# Sensor8A.net
KiCad netlist of a schematic drawn in EAGLE
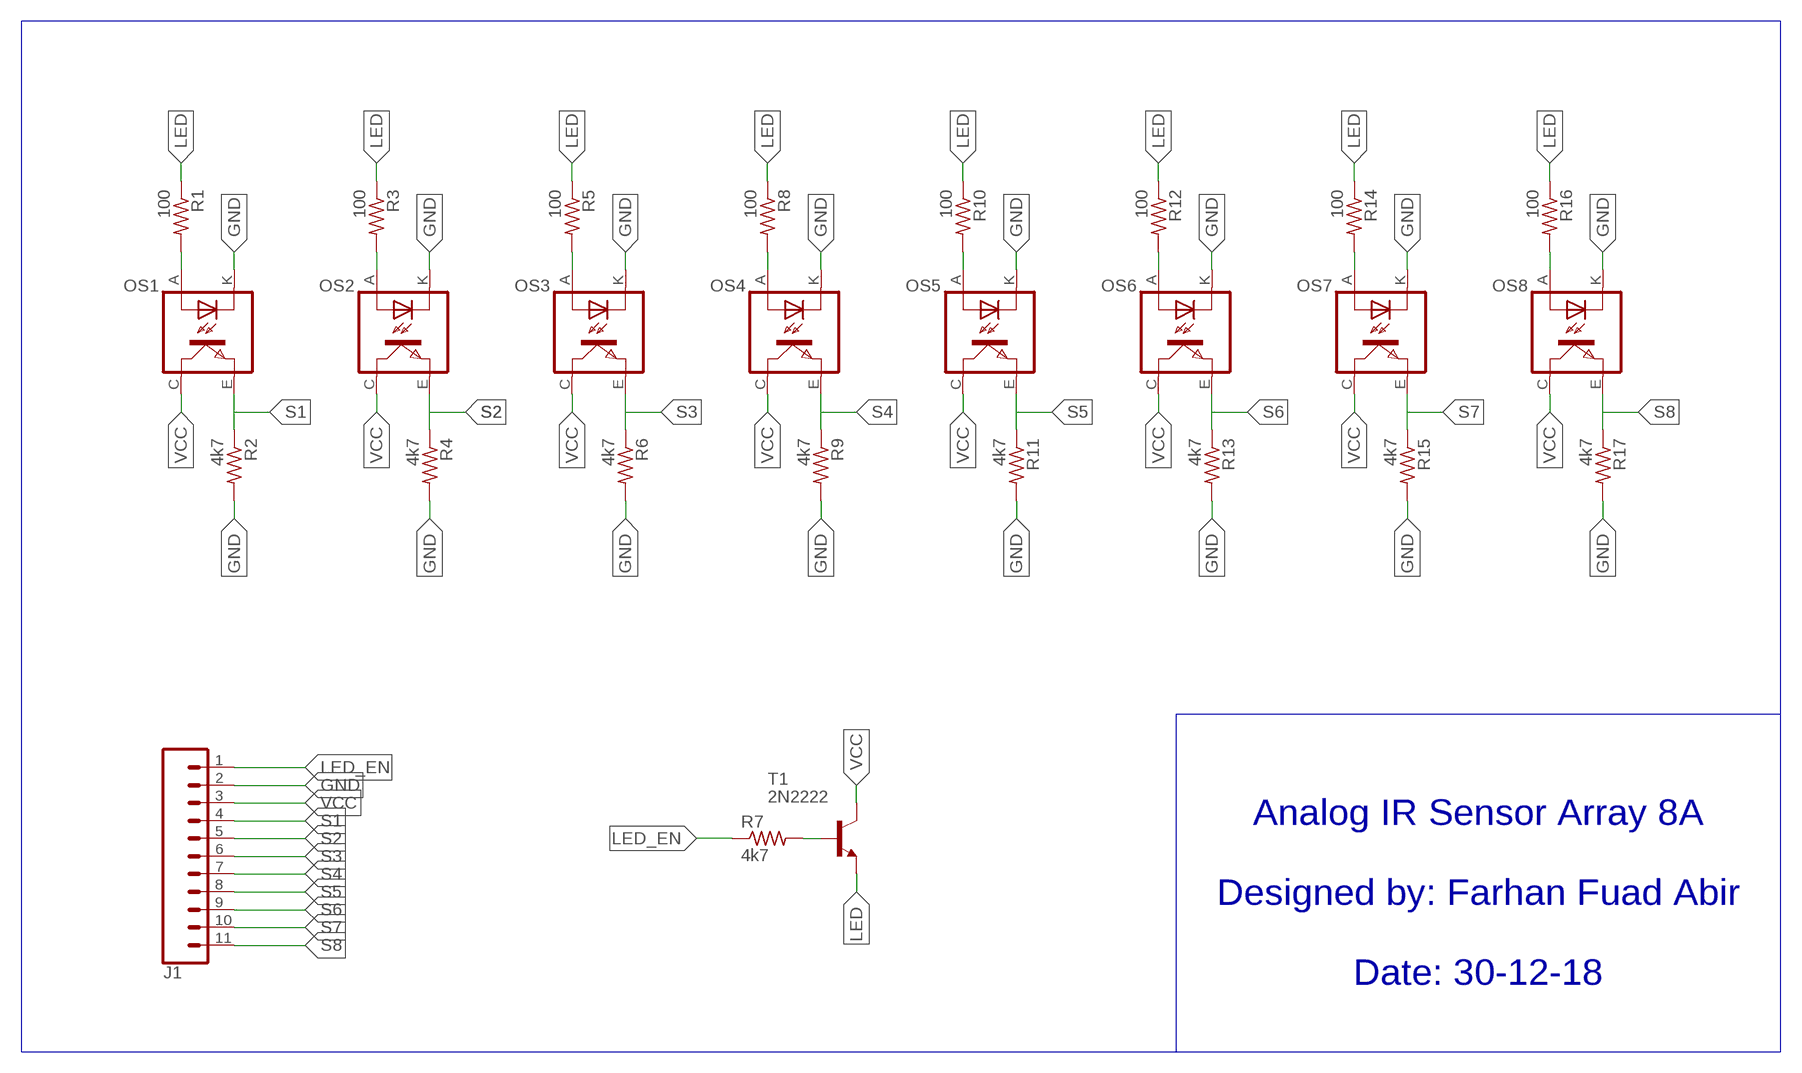
[diagram p0: schematic, sheet 1]

(export (version "E")
  (design (tool "Eeschema 10.0.6"))
  (components
    (comp (ref "J1")
      (value "CONN_11LONGPADS")
      (footprint "eagle-import:1X11_LONGPADS")
      (libsource (lib "eagle-import") (part "CONN_11LONGPADS"))
    )
    (comp (ref "OS1")
      (value "TCRT5000")
      (footprint "eagle-import:TCRT5000")
      (libsource (lib "eagle-import") (part "TCRT5000"))
    )
    (comp (ref "OS2")
      (value "TCRT5000")
      (footprint "eagle-import:TCRT5000")
      (libsource (lib "eagle-import") (part "TCRT5000"))
    )
    (comp (ref "OS3")
      (value "TCRT5000")
      (footprint "eagle-import:TCRT5000")
      (libsource (lib "eagle-import") (part "TCRT5000"))
    )
    (comp (ref "OS4")
      (value "TCRT5000")
      (footprint "eagle-import:TCRT5000")
      (libsource (lib "eagle-import") (part "TCRT5000"))
    )
    (comp (ref "OS5")
      (value "TCRT5000")
      (footprint "eagle-import:TCRT5000")
      (libsource (lib "eagle-import") (part "TCRT5000"))
    )
    (comp (ref "OS6")
      (value "TCRT5000")
      (footprint "eagle-import:TCRT5000")
      (libsource (lib "eagle-import") (part "TCRT5000"))
    )
    (comp (ref "OS7")
      (value "TCRT5000")
      (footprint "eagle-import:TCRT5000")
      (libsource (lib "eagle-import") (part "TCRT5000"))
    )
    (comp (ref "OS8")
      (value "TCRT5000")
      (footprint "eagle-import:TCRT5000")
      (libsource (lib "eagle-import") (part "TCRT5000"))
    )
    (comp (ref "R1")
      (value "100")
      (footprint "eagle-import:0204_7")
      (fields (field (name "SPICEPREFIX") "R"))
      (libsource (lib "eagle-import") (part "R-US_0204/7"))
    )
    (comp (ref "R2")
      (value "4k7")
      (footprint "eagle-import:0204_7")
      (fields (field (name "SPICEPREFIX") "R"))
      (libsource (lib "eagle-import") (part "R-US_0204/7"))
    )
    (comp (ref "R3")
      (value "100")
      (footprint "eagle-import:0204_7")
      (fields (field (name "SPICEPREFIX") "R"))
      (libsource (lib "eagle-import") (part "R-US_0204/7"))
    )
    (comp (ref "R4")
      (value "4k7")
      (footprint "eagle-import:0204_7")
      (fields (field (name "SPICEPREFIX") "R"))
      (libsource (lib "eagle-import") (part "R-US_0204/7"))
    )
    (comp (ref "R5")
      (value "100")
      (footprint "eagle-import:0204_7")
      (fields (field (name "SPICEPREFIX") "R"))
      (libsource (lib "eagle-import") (part "R-US_0204/7"))
    )
    (comp (ref "R6")
      (value "4k7")
      (footprint "eagle-import:0204_7")
      (fields (field (name "SPICEPREFIX") "R"))
      (libsource (lib "eagle-import") (part "R-US_0204/7"))
    )
    (comp (ref "R7")
      (value "4k7")
      (footprint "eagle-import:0204_7")
      (fields (field (name "SPICEPREFIX") "R"))
      (libsource (lib "eagle-import") (part "R-US_0204/7"))
    )
    (comp (ref "R8")
      (value "100")
      (footprint "eagle-import:0204_7")
      (fields (field (name "SPICEPREFIX") "R"))
      (libsource (lib "eagle-import") (part "R-US_0204/7"))
    )
    (comp (ref "R9")
      (value "4k7")
      (footprint "eagle-import:0204_7")
      (fields (field (name "SPICEPREFIX") "R"))
      (libsource (lib "eagle-import") (part "R-US_0204/7"))
    )
    (comp (ref "R10")
      (value "100")
      (footprint "eagle-import:0204_7")
      (fields (field (name "SPICEPREFIX") "R"))
      (libsource (lib "eagle-import") (part "R-US_0204/7"))
    )
    (comp (ref "R11")
      (value "4k7")
      (footprint "eagle-import:0204_7")
      (fields (field (name "SPICEPREFIX") "R"))
      (libsource (lib "eagle-import") (part "R-US_0204/7"))
    )
    (comp (ref "R12")
      (value "100")
      (footprint "eagle-import:0204_7")
      (fields (field (name "SPICEPREFIX") "R"))
      (libsource (lib "eagle-import") (part "R-US_0204/7"))
    )
    (comp (ref "R13")
      (value "4k7")
      (footprint "eagle-import:0204_7")
      (fields (field (name "SPICEPREFIX") "R"))
      (libsource (lib "eagle-import") (part "R-US_0204/7"))
    )
    (comp (ref "R14")
      (value "100")
      (footprint "eagle-import:0204_7")
      (fields (field (name "SPICEPREFIX") "R"))
      (libsource (lib "eagle-import") (part "R-US_0204/7"))
    )
    (comp (ref "R15")
      (value "4k7")
      (footprint "eagle-import:0204_7")
      (fields (field (name "SPICEPREFIX") "R"))
      (libsource (lib "eagle-import") (part "R-US_0204/7"))
    )
    (comp (ref "R16")
      (value "100")
      (footprint "eagle-import:0204_7")
      (fields (field (name "SPICEPREFIX") "R"))
      (libsource (lib "eagle-import") (part "R-US_0204/7"))
    )
    (comp (ref "R17")
      (value "4k7")
      (footprint "eagle-import:0204_7")
      (fields (field (name "SPICEPREFIX") "R"))
      (libsource (lib "eagle-import") (part "R-US_0204/7"))
    )
    (comp (ref "T1")
      (value "2N2222")
      (footprint "eagle-import:TO92-EBC-OVAL")
      (libsource (lib "eagle-import") (part "2N2222"))
    )
  )
  (nets
    (net (code "1") (name "GND") (class "Default")
      (node (ref "J1") (pin "2") (pinfunction "2_2") (pintype "passive"))
      (node (ref "OS1") (pin "K") (pinfunction "CATHODE_K") (pintype "passive"))
      (node (ref "OS2") (pin "K") (pinfunction "CATHODE_K") (pintype "passive"))
      (node (ref "OS3") (pin "K") (pinfunction "CATHODE_K") (pintype "passive"))
      (node (ref "OS4") (pin "K") (pinfunction "CATHODE_K") (pintype "passive"))
      (node (ref "OS5") (pin "K") (pinfunction "CATHODE_K") (pintype "passive"))
      (node (ref "OS6") (pin "K") (pinfunction "CATHODE_K") (pintype "passive"))
      (node (ref "OS7") (pin "K") (pinfunction "CATHODE_K") (pintype "passive"))
      (node (ref "OS8") (pin "K") (pinfunction "CATHODE_K") (pintype "passive"))
      (node (ref "R11") (pin "2") (pinfunction "2_2") (pintype "passive"))
      (node (ref "R13") (pin "2") (pinfunction "2_2") (pintype "passive"))
      (node (ref "R15") (pin "2") (pinfunction "2_2") (pintype "passive"))
      (node (ref "R17") (pin "2") (pinfunction "2_2") (pintype "passive"))
      (node (ref "R2") (pin "2") (pinfunction "2_2") (pintype "passive"))
      (node (ref "R4") (pin "2") (pinfunction "2_2") (pintype "passive"))
      (node (ref "R6") (pin "2") (pinfunction "2_2") (pintype "passive"))
      (node (ref "R9") (pin "2") (pinfunction "2_2") (pintype "passive"))
    )
    (net (code "2") (name "LED") (class "Default")
      (node (ref "R1") (pin "1") (pinfunction "1_1") (pintype "passive"))
      (node (ref "R10") (pin "1") (pinfunction "1_1") (pintype "passive"))
      (node (ref "R12") (pin "1") (pinfunction "1_1") (pintype "passive"))
      (node (ref "R14") (pin "1") (pinfunction "1_1") (pintype "passive"))
      (node (ref "R16") (pin "1") (pinfunction "1_1") (pintype "passive"))
      (node (ref "R3") (pin "1") (pinfunction "1_1") (pintype "passive"))
      (node (ref "R5") (pin "1") (pinfunction "1_1") (pintype "passive"))
      (node (ref "R8") (pin "1") (pinfunction "1_1") (pintype "passive"))
      (node (ref "T1") (pin "E") (pinfunction "E_E") (pintype "passive"))
    )
    (net (code "3") (name "LED_EN") (class "Default")
      (node (ref "J1") (pin "1") (pinfunction "1_1") (pintype "passive"))
      (node (ref "R7") (pin "1") (pinfunction "1_1") (pintype "passive"))
    )
    (net (code "4") (name "Net-(OS1-ANODE)") (class "Default")
      (node (ref "OS1") (pin "A") (pinfunction "ANODE_A") (pintype "passive"))
      (node (ref "R1") (pin "2") (pinfunction "2_2") (pintype "passive"))
    )
    (net (code "5") (name "Net-(OS2-ANODE)") (class "Default")
      (node (ref "OS2") (pin "A") (pinfunction "ANODE_A") (pintype "passive"))
      (node (ref "R3") (pin "2") (pinfunction "2_2") (pintype "passive"))
    )
    (net (code "6") (name "Net-(OS3-ANODE)") (class "Default")
      (node (ref "OS3") (pin "A") (pinfunction "ANODE_A") (pintype "passive"))
      (node (ref "R5") (pin "2") (pinfunction "2_2") (pintype "passive"))
    )
    (net (code "7") (name "Net-(OS4-ANODE)") (class "Default")
      (node (ref "OS4") (pin "A") (pinfunction "ANODE_A") (pintype "passive"))
      (node (ref "R8") (pin "2") (pinfunction "2_2") (pintype "passive"))
    )
    (net (code "8") (name "Net-(OS5-ANODE)") (class "Default")
      (node (ref "OS5") (pin "A") (pinfunction "ANODE_A") (pintype "passive"))
      (node (ref "R10") (pin "2") (pinfunction "2_2") (pintype "passive"))
    )
    (net (code "9") (name "Net-(OS6-ANODE)") (class "Default")
      (node (ref "OS6") (pin "A") (pinfunction "ANODE_A") (pintype "passive"))
      (node (ref "R12") (pin "2") (pinfunction "2_2") (pintype "passive"))
    )
    (net (code "10") (name "Net-(OS7-ANODE)") (class "Default")
      (node (ref "OS7") (pin "A") (pinfunction "ANODE_A") (pintype "passive"))
      (node (ref "R14") (pin "2") (pinfunction "2_2") (pintype "passive"))
    )
    (net (code "11") (name "Net-(OS8-ANODE)") (class "Default")
      (node (ref "OS8") (pin "A") (pinfunction "ANODE_A") (pintype "passive"))
      (node (ref "R16") (pin "2") (pinfunction "2_2") (pintype "passive"))
    )
    (net (code "12") (name "Net-(R7-Pad2)") (class "Default")
      (node (ref "R7") (pin "2") (pinfunction "2_2") (pintype "passive"))
      (node (ref "T1") (pin "B") (pinfunction "B_B") (pintype "passive"))
    )
    (net (code "13") (name "S1") (class "Default")
      (node (ref "J1") (pin "4") (pinfunction "4_4") (pintype "passive"))
      (node (ref "OS1") (pin "E") (pinfunction "EMITTER_E") (pintype "passive"))
      (node (ref "R2") (pin "1") (pinfunction "1_1") (pintype "passive"))
    )
    (net (code "14") (name "S2") (class "Default")
      (node (ref "J1") (pin "5") (pinfunction "5_5") (pintype "passive"))
      (node (ref "OS2") (pin "E") (pinfunction "EMITTER_E") (pintype "passive"))
      (node (ref "R4") (pin "1") (pinfunction "1_1") (pintype "passive"))
    )
    (net (code "15") (name "S3") (class "Default")
      (node (ref "J1") (pin "6") (pinfunction "6_6") (pintype "passive"))
      (node (ref "OS3") (pin "E") (pinfunction "EMITTER_E") (pintype "passive"))
      (node (ref "R6") (pin "1") (pinfunction "1_1") (pintype "passive"))
    )
    (net (code "16") (name "S4") (class "Default")
      (node (ref "J1") (pin "7") (pinfunction "7_7") (pintype "passive"))
      (node (ref "OS4") (pin "E") (pinfunction "EMITTER_E") (pintype "passive"))
      (node (ref "R9") (pin "1") (pinfunction "1_1") (pintype "passive"))
    )
    (net (code "17") (name "S5") (class "Default")
      (node (ref "J1") (pin "8") (pinfunction "8_8") (pintype "passive"))
      (node (ref "OS5") (pin "E") (pinfunction "EMITTER_E") (pintype "passive"))
      (node (ref "R11") (pin "1") (pinfunction "1_1") (pintype "passive"))
    )
    (net (code "18") (name "S6") (class "Default")
      (node (ref "J1") (pin "9") (pinfunction "9_9") (pintype "passive"))
      (node (ref "OS6") (pin "E") (pinfunction "EMITTER_E") (pintype "passive"))
      (node (ref "R13") (pin "1") (pinfunction "1_1") (pintype "passive"))
    )
    (net (code "19") (name "S7") (class "Default")
      (node (ref "J1") (pin "10") (pinfunction "10_10") (pintype "passive"))
      (node (ref "OS7") (pin "E") (pinfunction "EMITTER_E") (pintype "passive"))
      (node (ref "R15") (pin "1") (pinfunction "1_1") (pintype "passive"))
    )
    (net (code "20") (name "S8") (class "Default")
      (node (ref "J1") (pin "11") (pinfunction "11_11") (pintype "passive"))
      (node (ref "OS8") (pin "E") (pinfunction "EMITTER_E") (pintype "passive"))
      (node (ref "R17") (pin "1") (pinfunction "1_1") (pintype "passive"))
    )
    (net (code "21") (name "VCC") (class "Default")
      (node (ref "J1") (pin "3") (pinfunction "3_3") (pintype "passive"))
      (node (ref "OS1") (pin "C") (pinfunction "COLLECTOR_C") (pintype "passive"))
      (node (ref "OS2") (pin "C") (pinfunction "COLLECTOR_C") (pintype "passive"))
      (node (ref "OS3") (pin "C") (pinfunction "COLLECTOR_C") (pintype "passive"))
      (node (ref "OS4") (pin "C") (pinfunction "COLLECTOR_C") (pintype "passive"))
      (node (ref "OS5") (pin "C") (pinfunction "COLLECTOR_C") (pintype "passive"))
      (node (ref "OS6") (pin "C") (pinfunction "COLLECTOR_C") (pintype "passive"))
      (node (ref "OS7") (pin "C") (pinfunction "COLLECTOR_C") (pintype "passive"))
      (node (ref "OS8") (pin "C") (pinfunction "COLLECTOR_C") (pintype "passive"))
      (node (ref "T1") (pin "C") (pinfunction "C_C") (pintype "passive"))
    )
  )
)
